# super7e.net
KiCad netlist of a schematic drawn in EAGLE
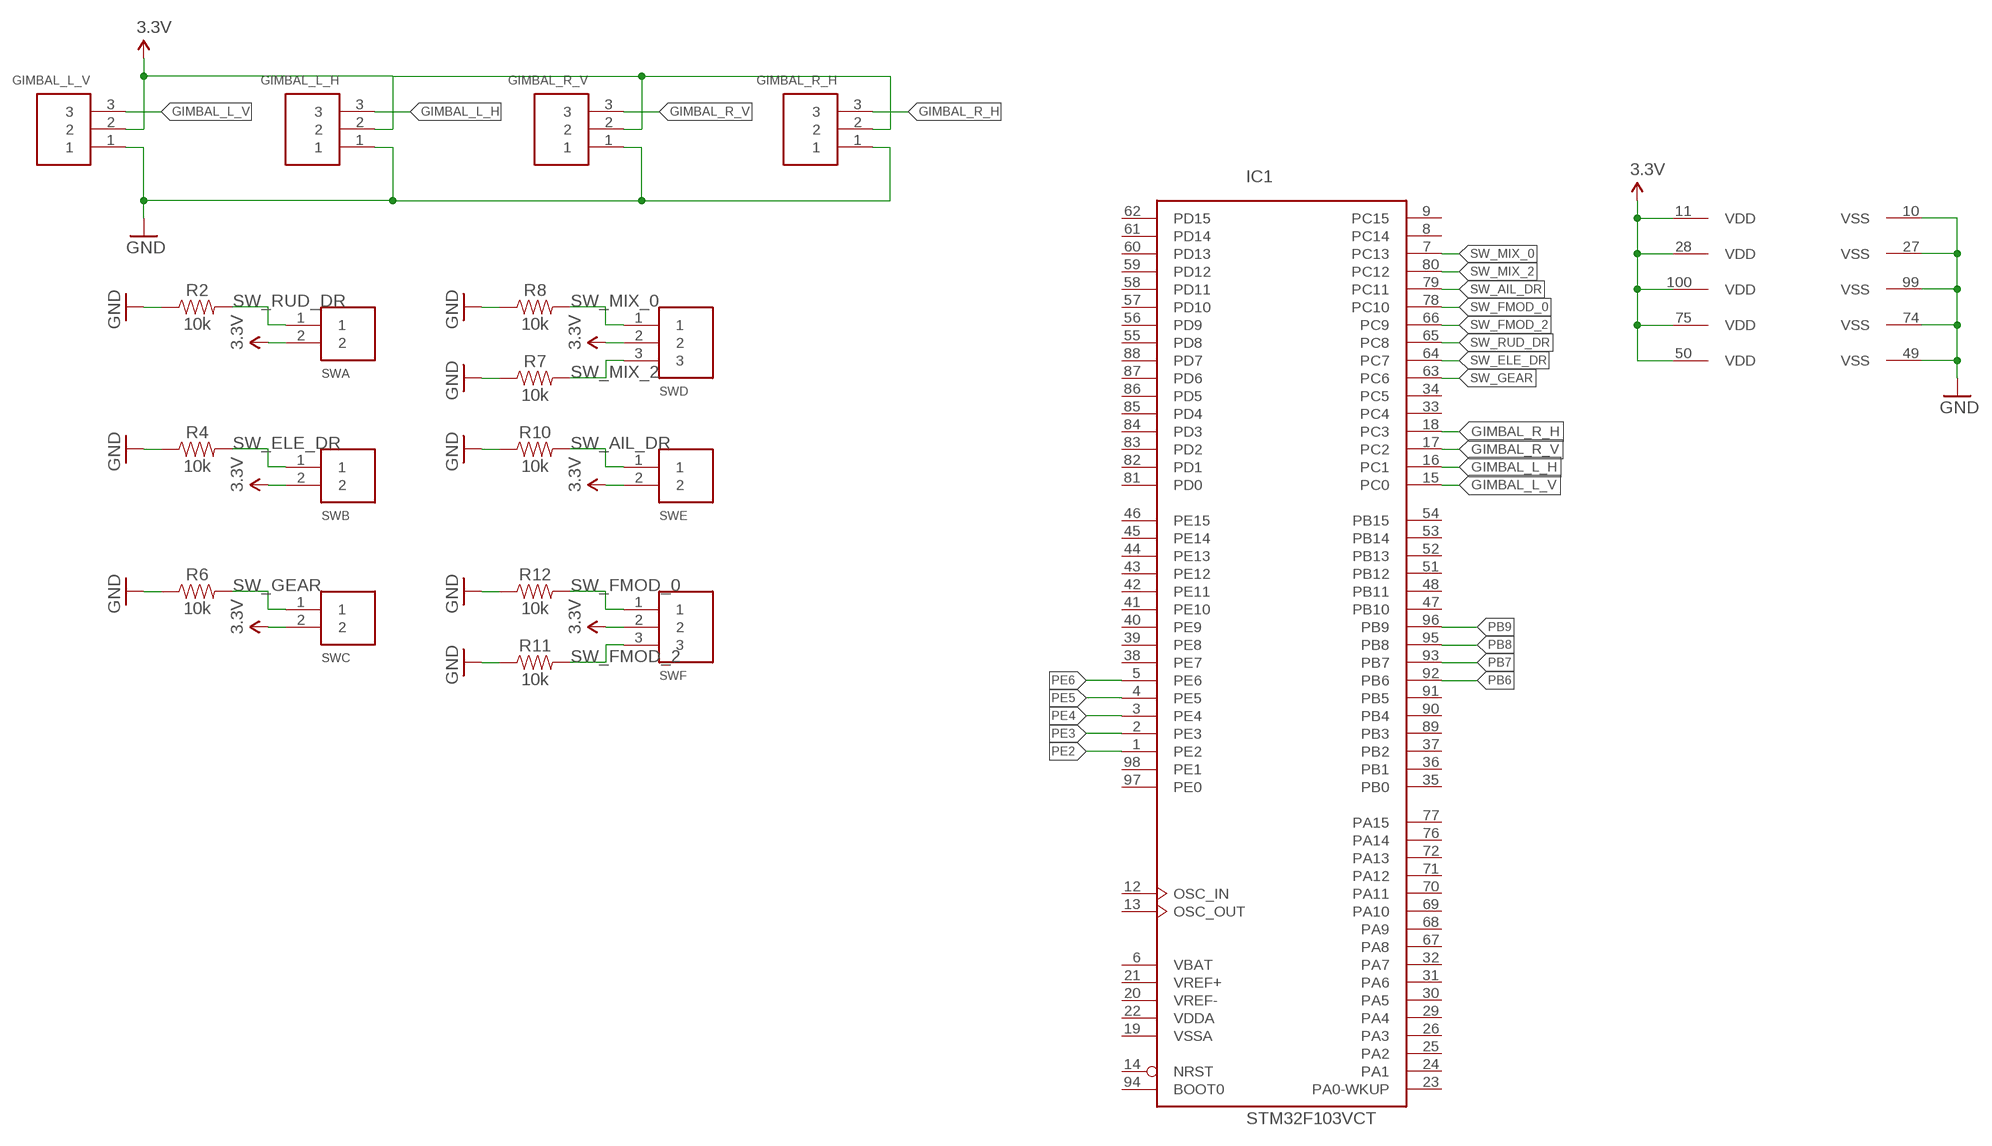
[diagram p0: schematic, sheet 1]

(export (version "E")
  (design (tool "Eeschema 10.0.6"))
  (components
    (comp (ref "GIMBAL_L_H")
      (value "3PIN")
      (footprint "eagle-import:B3B-PH-K-S")
      (libsource (lib "eagle-import") (part "3PIN"))
    )
    (comp (ref "GIMBAL_L_V")
      (value "3PIN")
      (footprint "eagle-import:B3B-PH-K-S")
      (libsource (lib "eagle-import") (part "3PIN"))
    )
    (comp (ref "GIMBAL_R_H")
      (value "3PIN")
      (footprint "eagle-import:B3B-PH-K-S")
      (libsource (lib "eagle-import") (part "3PIN"))
    )
    (comp (ref "GIMBAL_R_V")
      (value "3PIN")
      (footprint "eagle-import:B3B-PH-K-S")
      (libsource (lib "eagle-import") (part "3PIN"))
    )
    (comp (ref "IC1")
      (value "STM32F103VCT")
      (footprint "eagle-import:LQFP100")
      (libsource (lib "eagle-import") (part "STM32F103VTC"))
    )
    (comp (ref "R2")
      (value "10k")
      (footprint "eagle-import:0603")
      (libsource (lib "eagle-import") (part "10KOHM-0603-1/10W-1%"))
    )
    (comp (ref "R4")
      (value "10k")
      (footprint "eagle-import:0603")
      (libsource (lib "eagle-import") (part "10KOHM-0603-1/10W-1%"))
    )
    (comp (ref "R6")
      (value "10k")
      (footprint "eagle-import:0603")
      (libsource (lib "eagle-import") (part "10KOHM-0603-1/10W-1%"))
    )
    (comp (ref "R7")
      (value "10k")
      (footprint "eagle-import:0603")
      (libsource (lib "eagle-import") (part "10KOHM-0603-1/10W-1%"))
    )
    (comp (ref "R8")
      (value "10k")
      (footprint "eagle-import:0603")
      (libsource (lib "eagle-import") (part "10KOHM-0603-1/10W-1%"))
    )
    (comp (ref "R10")
      (value "10k")
      (footprint "eagle-import:0603")
      (libsource (lib "eagle-import") (part "10KOHM-0603-1/10W-1%"))
    )
    (comp (ref "R11")
      (value "10k")
      (footprint "eagle-import:0603")
      (libsource (lib "eagle-import") (part "10KOHM-0603-1/10W-1%"))
    )
    (comp (ref "R12")
      (value "10k")
      (footprint "eagle-import:0603")
      (libsource (lib "eagle-import") (part "10KOHM-0603-1/10W-1%"))
    )
    (comp (ref "SWA")
      (value "2PIN")
      (footprint "eagle-import:B2B-PH-K-S")
      (libsource (lib "eagle-import") (part "2PIN"))
    )
    (comp (ref "SWB")
      (value "2PIN")
      (footprint "eagle-import:B2B-PH-K-S")
      (libsource (lib "eagle-import") (part "2PIN"))
    )
    (comp (ref "SWC")
      (value "2PIN")
      (footprint "eagle-import:B2B-PH-K-S")
      (libsource (lib "eagle-import") (part "2PIN"))
    )
    (comp (ref "SWD")
      (value "3PIN")
      (footprint "eagle-import:B3B-PH-K-S")
      (libsource (lib "eagle-import") (part "3PIN"))
    )
    (comp (ref "SWE")
      (value "2PIN")
      (footprint "eagle-import:B2B-PH-K-S")
      (libsource (lib "eagle-import") (part "2PIN"))
    )
    (comp (ref "SWF")
      (value "3PIN")
      (footprint "eagle-import:B3B-PH-K-S")
      (libsource (lib "eagle-import") (part "3PIN"))
    )
  )
  (nets
    (net (code "1") (name "/VBAT") (class "Default")
      (node (ref "IC1") (pin "6") (pinfunction "VBAT_6") (pintype "power_in"))
    )
    (net (code "2") (name "/VDDA") (class "Default")
      (node (ref "IC1") (pin "22") (pinfunction "VDDA_22") (pintype "power_in"))
    )
    (net (code "3") (name "/VREF+") (class "Default")
      (node (ref "IC1") (pin "21") (pinfunction "VREF+_21") (pintype "power_in"))
    )
    (net (code "4") (name "/VREF-") (class "Default")
      (node (ref "IC1") (pin "20") (pinfunction "VREF-_20") (pintype "power_in"))
    )
    (net (code "5") (name "/VSSA") (class "Default")
      (node (ref "IC1") (pin "19") (pinfunction "VSSA_19") (pintype "power_in"))
    )
    (net (code "6") (name "3.3V") (class "Default")
      (node (ref "GIMBAL_L_H") (pin "2") (pinfunction "2_2") (pintype "bidirectional"))
      (node (ref "GIMBAL_L_V") (pin "2") (pinfunction "2_2") (pintype "bidirectional"))
      (node (ref "GIMBAL_R_H") (pin "2") (pinfunction "2_2") (pintype "bidirectional"))
      (node (ref "GIMBAL_R_V") (pin "2") (pinfunction "2_2") (pintype "bidirectional"))
      (node (ref "IC1") (pin "100") (pinfunction "VDD_100") (pintype "power_in"))
      (node (ref "IC1") (pin "11") (pinfunction "VDD_11") (pintype "power_in"))
      (node (ref "IC1") (pin "28") (pinfunction "VDD_28") (pintype "power_in"))
      (node (ref "IC1") (pin "50") (pinfunction "VDD_50") (pintype "power_in"))
      (node (ref "IC1") (pin "75") (pinfunction "VDD_75") (pintype "power_in"))
      (node (ref "SWA") (pin "2") (pinfunction "2_2") (pintype "bidirectional"))
      (node (ref "SWB") (pin "2") (pinfunction "2_2") (pintype "bidirectional"))
      (node (ref "SWC") (pin "2") (pinfunction "2_2") (pintype "bidirectional"))
      (node (ref "SWD") (pin "2") (pinfunction "2_2") (pintype "bidirectional"))
      (node (ref "SWE") (pin "2") (pinfunction "2_2") (pintype "bidirectional"))
      (node (ref "SWF") (pin "2") (pinfunction "2_2") (pintype "bidirectional"))
    )
    (net (code "7") (name "GIMBAL_L_H") (class "Default")
      (node (ref "GIMBAL_L_H") (pin "3") (pinfunction "3_3") (pintype "bidirectional"))
      (node (ref "IC1") (pin "16") (pinfunction "PC1_16") (pintype "bidirectional"))
    )
    (net (code "8") (name "GIMBAL_L_V") (class "Default")
      (node (ref "GIMBAL_L_V") (pin "3") (pinfunction "3_3") (pintype "bidirectional"))
      (node (ref "IC1") (pin "15") (pinfunction "PC0_15") (pintype "bidirectional"))
    )
    (net (code "9") (name "GIMBAL_R_H") (class "Default")
      (node (ref "GIMBAL_R_H") (pin "3") (pinfunction "3_3") (pintype "bidirectional"))
      (node (ref "IC1") (pin "18") (pinfunction "PC3_18") (pintype "bidirectional"))
    )
    (net (code "10") (name "GIMBAL_R_V") (class "Default")
      (node (ref "GIMBAL_R_V") (pin "3") (pinfunction "3_3") (pintype "bidirectional"))
      (node (ref "IC1") (pin "17") (pinfunction "PC2_17") (pintype "bidirectional"))
    )
    (net (code "11") (name "GND") (class "Default")
      (node (ref "GIMBAL_L_H") (pin "1") (pinfunction "1_1") (pintype "bidirectional"))
      (node (ref "GIMBAL_L_V") (pin "1") (pinfunction "1_1") (pintype "bidirectional"))
      (node (ref "GIMBAL_R_H") (pin "1") (pinfunction "1_1") (pintype "bidirectional"))
      (node (ref "GIMBAL_R_V") (pin "1") (pinfunction "1_1") (pintype "bidirectional"))
      (node (ref "IC1") (pin "10") (pinfunction "VSS_10") (pintype "power_in"))
      (node (ref "IC1") (pin "27") (pinfunction "VSS_27") (pintype "power_in"))
      (node (ref "IC1") (pin "49") (pinfunction "VSS_49") (pintype "power_in"))
      (node (ref "IC1") (pin "74") (pinfunction "VSS_74") (pintype "power_in"))
      (node (ref "IC1") (pin "99") (pinfunction "VSS_99") (pintype "power_in"))
      (node (ref "R10") (pin "1") (pinfunction "1_1") (pintype "passive"))
      (node (ref "R11") (pin "1") (pinfunction "1_1") (pintype "passive"))
      (node (ref "R12") (pin "1") (pinfunction "1_1") (pintype "passive"))
      (node (ref "R2") (pin "1") (pinfunction "1_1") (pintype "passive"))
      (node (ref "R4") (pin "1") (pinfunction "1_1") (pintype "passive"))
      (node (ref "R6") (pin "1") (pinfunction "1_1") (pintype "passive"))
      (node (ref "R7") (pin "1") (pinfunction "1_1") (pintype "passive"))
      (node (ref "R8") (pin "1") (pinfunction "1_1") (pintype "passive"))
    )
    (net (code "12") (name "PB6") (class "Default")
      (node (ref "IC1") (pin "92") (pinfunction "PB6_92") (pintype "bidirectional"))
    )
    (net (code "13") (name "PB7") (class "Default")
      (node (ref "IC1") (pin "93") (pinfunction "PB7_93") (pintype "bidirectional"))
    )
    (net (code "14") (name "PB8") (class "Default")
      (node (ref "IC1") (pin "95") (pinfunction "PB8_95") (pintype "bidirectional"))
    )
    (net (code "15") (name "PB9") (class "Default")
      (node (ref "IC1") (pin "96") (pinfunction "PB9_96") (pintype "bidirectional"))
    )
    (net (code "16") (name "PE2") (class "Default")
      (node (ref "IC1") (pin "1") (pinfunction "PE2_1") (pintype "bidirectional"))
    )
    (net (code "17") (name "PE3") (class "Default")
      (node (ref "IC1") (pin "2") (pinfunction "PE3_2") (pintype "bidirectional"))
    )
    (net (code "18") (name "PE4") (class "Default")
      (node (ref "IC1") (pin "3") (pinfunction "PE4_3") (pintype "bidirectional"))
    )
    (net (code "19") (name "PE5") (class "Default")
      (node (ref "IC1") (pin "4") (pinfunction "PE5_4") (pintype "bidirectional"))
    )
    (net (code "20") (name "PE6") (class "Default")
      (node (ref "IC1") (pin "5") (pinfunction "PE6_5") (pintype "bidirectional"))
    )
    (net (code "21") (name "SW_AIL_DR") (class "Default")
      (node (ref "IC1") (pin "79") (pinfunction "PC11_79") (pintype "bidirectional"))
      (node (ref "R10") (pin "2") (pinfunction "2_2") (pintype "passive"))
      (node (ref "SWE") (pin "1") (pinfunction "1_1") (pintype "bidirectional"))
    )
    (net (code "22") (name "SW_ELE_DR") (class "Default")
      (node (ref "IC1") (pin "64") (pinfunction "PC7_64") (pintype "bidirectional"))
      (node (ref "R4") (pin "2") (pinfunction "2_2") (pintype "passive"))
      (node (ref "SWB") (pin "1") (pinfunction "1_1") (pintype "bidirectional"))
    )
    (net (code "23") (name "SW_FMOD_0") (class "Default")
      (node (ref "IC1") (pin "78") (pinfunction "PC10_78") (pintype "bidirectional"))
      (node (ref "R12") (pin "2") (pinfunction "2_2") (pintype "passive"))
      (node (ref "SWF") (pin "1") (pinfunction "1_1") (pintype "bidirectional"))
    )
    (net (code "24") (name "SW_FMOD_2") (class "Default")
      (node (ref "IC1") (pin "66") (pinfunction "PC9_66") (pintype "bidirectional"))
      (node (ref "R11") (pin "2") (pinfunction "2_2") (pintype "passive"))
      (node (ref "SWF") (pin "3") (pinfunction "3_3") (pintype "bidirectional"))
    )
    (net (code "25") (name "SW_GEAR") (class "Default")
      (node (ref "IC1") (pin "63") (pinfunction "PC6_63") (pintype "bidirectional"))
      (node (ref "R6") (pin "2") (pinfunction "2_2") (pintype "passive"))
      (node (ref "SWC") (pin "1") (pinfunction "1_1") (pintype "bidirectional"))
    )
    (net (code "26") (name "SW_MIX_0") (class "Default")
      (node (ref "IC1") (pin "7") (pinfunction "PC13_7") (pintype "bidirectional"))
      (node (ref "R8") (pin "2") (pinfunction "2_2") (pintype "passive"))
      (node (ref "SWD") (pin "1") (pinfunction "1_1") (pintype "bidirectional"))
    )
    (net (code "27") (name "SW_MIX_2") (class "Default")
      (node (ref "IC1") (pin "80") (pinfunction "PC12_80") (pintype "bidirectional"))
      (node (ref "R7") (pin "2") (pinfunction "2_2") (pintype "passive"))
      (node (ref "SWD") (pin "3") (pinfunction "3_3") (pintype "bidirectional"))
    )
    (net (code "28") (name "SW_RUD_DR") (class "Default")
      (node (ref "IC1") (pin "65") (pinfunction "PC8_65") (pintype "bidirectional"))
      (node (ref "R2") (pin "2") (pinfunction "2_2") (pintype "passive"))
      (node (ref "SWA") (pin "1") (pinfunction "1_1") (pintype "bidirectional"))
    )
    (net (code "29") (name "unconnected-(IC1A-BOOT0-Pad94)") (class "Default")
      (node (ref "IC1") (pin "94") (pinfunction "BOOT0_94") (pintype "input"))
    )
    (net (code "30") (name "unconnected-(IC1A-NRST-Pad14)") (class "Default")
      (node (ref "IC1") (pin "14") (pinfunction "NRST_14") (pintype "bidirectional"))
    )
    (net (code "31") (name "unconnected-(IC1A-OSC_IN-Pad12)") (class "Default")
      (node (ref "IC1") (pin "12") (pinfunction "OSC_IN_12") (pintype "bidirectional"))
    )
    (net (code "32") (name "unconnected-(IC1A-OSC_OUT-Pad13)") (class "Default")
      (node (ref "IC1") (pin "13") (pinfunction "OSC_OUT_13") (pintype "bidirectional"))
    )
    (net (code "33") (name "unconnected-(IC1A-PA0-WKUP-Pad23)") (class "Default")
      (node (ref "IC1") (pin "23") (pinfunction "PA0-WKUP_23") (pintype "bidirectional"))
    )
    (net (code "34") (name "unconnected-(IC1A-PA1-Pad24)") (class "Default")
      (node (ref "IC1") (pin "24") (pinfunction "PA1_24") (pintype "bidirectional"))
    )
    (net (code "35") (name "unconnected-(IC1A-PA2-Pad25)") (class "Default")
      (node (ref "IC1") (pin "25") (pinfunction "PA2_25") (pintype "bidirectional"))
    )
    (net (code "36") (name "unconnected-(IC1A-PA3-Pad26)") (class "Default")
      (node (ref "IC1") (pin "26") (pinfunction "PA3_26") (pintype "bidirectional"))
    )
    (net (code "37") (name "unconnected-(IC1A-PA4-Pad29)") (class "Default")
      (node (ref "IC1") (pin "29") (pinfunction "PA4_29") (pintype "bidirectional"))
    )
    (net (code "38") (name "unconnected-(IC1A-PA5-Pad30)") (class "Default")
      (node (ref "IC1") (pin "30") (pinfunction "PA5_30") (pintype "bidirectional"))
    )
    (net (code "39") (name "unconnected-(IC1A-PA6-Pad31)") (class "Default")
      (node (ref "IC1") (pin "31") (pinfunction "PA6_31") (pintype "bidirectional"))
    )
    (net (code "40") (name "unconnected-(IC1A-PA7-Pad32)") (class "Default")
      (node (ref "IC1") (pin "32") (pinfunction "PA7_32") (pintype "bidirectional"))
    )
    (net (code "41") (name "unconnected-(IC1A-PA8-Pad67)") (class "Default")
      (node (ref "IC1") (pin "67") (pinfunction "PA8_67") (pintype "bidirectional"))
    )
    (net (code "42") (name "unconnected-(IC1A-PA9-Pad68)") (class "Default")
      (node (ref "IC1") (pin "68") (pinfunction "PA9_68") (pintype "bidirectional"))
    )
    (net (code "43") (name "unconnected-(IC1A-PA10-Pad69)") (class "Default")
      (node (ref "IC1") (pin "69") (pinfunction "PA10_69") (pintype "bidirectional"))
    )
    (net (code "44") (name "unconnected-(IC1A-PA11-Pad70)") (class "Default")
      (node (ref "IC1") (pin "70") (pinfunction "PA11_70") (pintype "bidirectional"))
    )
    (net (code "45") (name "unconnected-(IC1A-PA12-Pad71)") (class "Default")
      (node (ref "IC1") (pin "71") (pinfunction "PA12_71") (pintype "bidirectional"))
    )
    (net (code "46") (name "unconnected-(IC1A-PA13-Pad72)") (class "Default")
      (node (ref "IC1") (pin "72") (pinfunction "PA13_72") (pintype "bidirectional"))
    )
    (net (code "47") (name "unconnected-(IC1A-PA14-Pad76)") (class "Default")
      (node (ref "IC1") (pin "76") (pinfunction "PA14_76") (pintype "bidirectional"))
    )
    (net (code "48") (name "unconnected-(IC1A-PA15-Pad77)") (class "Default")
      (node (ref "IC1") (pin "77") (pinfunction "PA15_77") (pintype "bidirectional"))
    )
    (net (code "49") (name "unconnected-(IC1A-PB0-Pad35)") (class "Default")
      (node (ref "IC1") (pin "35") (pinfunction "PB0_35") (pintype "bidirectional"))
    )
    (net (code "50") (name "unconnected-(IC1A-PB1-Pad36)") (class "Default")
      (node (ref "IC1") (pin "36") (pinfunction "PB1_36") (pintype "bidirectional"))
    )
    (net (code "51") (name "unconnected-(IC1A-PB2-Pad37)") (class "Default")
      (node (ref "IC1") (pin "37") (pinfunction "PB2_37") (pintype "bidirectional"))
    )
    (net (code "52") (name "unconnected-(IC1A-PB3-Pad89)") (class "Default")
      (node (ref "IC1") (pin "89") (pinfunction "PB3_89") (pintype "bidirectional"))
    )
    (net (code "53") (name "unconnected-(IC1A-PB4-Pad90)") (class "Default")
      (node (ref "IC1") (pin "90") (pinfunction "PB4_90") (pintype "bidirectional"))
    )
    (net (code "54") (name "unconnected-(IC1A-PB5-Pad91)") (class "Default")
      (node (ref "IC1") (pin "91") (pinfunction "PB5_91") (pintype "bidirectional"))
    )
    (net (code "55") (name "unconnected-(IC1A-PB10-Pad47)") (class "Default")
      (node (ref "IC1") (pin "47") (pinfunction "PB10_47") (pintype "bidirectional"))
    )
    (net (code "56") (name "unconnected-(IC1A-PB11-Pad48)") (class "Default")
      (node (ref "IC1") (pin "48") (pinfunction "PB11_48") (pintype "bidirectional"))
    )
    (net (code "57") (name "unconnected-(IC1A-PB12-Pad51)") (class "Default")
      (node (ref "IC1") (pin "51") (pinfunction "PB12_51") (pintype "bidirectional"))
    )
    (net (code "58") (name "unconnected-(IC1A-PB13-Pad52)") (class "Default")
      (node (ref "IC1") (pin "52") (pinfunction "PB13_52") (pintype "bidirectional"))
    )
    (net (code "59") (name "unconnected-(IC1A-PB14-Pad53)") (class "Default")
      (node (ref "IC1") (pin "53") (pinfunction "PB14_53") (pintype "bidirectional"))
    )
    (net (code "60") (name "unconnected-(IC1A-PB15-Pad54)") (class "Default")
      (node (ref "IC1") (pin "54") (pinfunction "PB15_54") (pintype "bidirectional"))
    )
    (net (code "61") (name "unconnected-(IC1A-PC4-Pad33)") (class "Default")
      (node (ref "IC1") (pin "33") (pinfunction "PC4_33") (pintype "bidirectional"))
    )
    (net (code "62") (name "unconnected-(IC1A-PC5-Pad34)") (class "Default")
      (node (ref "IC1") (pin "34") (pinfunction "PC5_34") (pintype "bidirectional"))
    )
    (net (code "63") (name "unconnected-(IC1A-PC14-Pad8)") (class "Default")
      (node (ref "IC1") (pin "8") (pinfunction "PC14_8") (pintype "bidirectional"))
    )
    (net (code "64") (name "unconnected-(IC1A-PC15-Pad9)") (class "Default")
      (node (ref "IC1") (pin "9") (pinfunction "PC15_9") (pintype "bidirectional"))
    )
    (net (code "65") (name "unconnected-(IC1A-PD0-Pad81)") (class "Default")
      (node (ref "IC1") (pin "81") (pinfunction "PD0_81") (pintype "bidirectional"))
    )
    (net (code "66") (name "unconnected-(IC1A-PD1-Pad82)") (class "Default")
      (node (ref "IC1") (pin "82") (pinfunction "PD1_82") (pintype "bidirectional"))
    )
    (net (code "67") (name "unconnected-(IC1A-PD2-Pad83)") (class "Default")
      (node (ref "IC1") (pin "83") (pinfunction "PD2_83") (pintype "bidirectional"))
    )
    (net (code "68") (name "unconnected-(IC1A-PD3-Pad84)") (class "Default")
      (node (ref "IC1") (pin "84") (pinfunction "PD3_84") (pintype "bidirectional"))
    )
    (net (code "69") (name "unconnected-(IC1A-PD4-Pad85)") (class "Default")
      (node (ref "IC1") (pin "85") (pinfunction "PD4_85") (pintype "bidirectional"))
    )
    (net (code "70") (name "unconnected-(IC1A-PD5-Pad86)") (class "Default")
      (node (ref "IC1") (pin "86") (pinfunction "PD5_86") (pintype "bidirectional"))
    )
    (net (code "71") (name "unconnected-(IC1A-PD6-Pad87)") (class "Default")
      (node (ref "IC1") (pin "87") (pinfunction "PD6_87") (pintype "bidirectional"))
    )
    (net (code "72") (name "unconnected-(IC1A-PD7-Pad88)") (class "Default")
      (node (ref "IC1") (pin "88") (pinfunction "PD7_88") (pintype "bidirectional"))
    )
    (net (code "73") (name "unconnected-(IC1A-PD8-Pad55)") (class "Default")
      (node (ref "IC1") (pin "55") (pinfunction "PD8_55") (pintype "bidirectional"))
    )
    (net (code "74") (name "unconnected-(IC1A-PD9-Pad56)") (class "Default")
      (node (ref "IC1") (pin "56") (pinfunction "PD9_56") (pintype "bidirectional"))
    )
    (net (code "75") (name "unconnected-(IC1A-PD10-Pad57)") (class "Default")
      (node (ref "IC1") (pin "57") (pinfunction "PD10_57") (pintype "bidirectional"))
    )
    (net (code "76") (name "unconnected-(IC1A-PD11-Pad58)") (class "Default")
      (node (ref "IC1") (pin "58") (pinfunction "PD11_58") (pintype "bidirectional"))
    )
    (net (code "77") (name "unconnected-(IC1A-PD12-Pad59)") (class "Default")
      (node (ref "IC1") (pin "59") (pinfunction "PD12_59") (pintype "bidirectional"))
    )
    (net (code "78") (name "unconnected-(IC1A-PD13-Pad60)") (class "Default")
      (node (ref "IC1") (pin "60") (pinfunction "PD13_60") (pintype "bidirectional"))
    )
    (net (code "79") (name "unconnected-(IC1A-PD14-Pad61)") (class "Default")
      (node (ref "IC1") (pin "61") (pinfunction "PD14_61") (pintype "bidirectional"))
    )
    (net (code "80") (name "unconnected-(IC1A-PD15-Pad62)") (class "Default")
      (node (ref "IC1") (pin "62") (pinfunction "PD15_62") (pintype "bidirectional"))
    )
    (net (code "81") (name "unconnected-(IC1A-PE0-Pad97)") (class "Default")
      (node (ref "IC1") (pin "97") (pinfunction "PE0_97") (pintype "bidirectional"))
    )
    (net (code "82") (name "unconnected-(IC1A-PE1-Pad98)") (class "Default")
      (node (ref "IC1") (pin "98") (pinfunction "PE1_98") (pintype "bidirectional"))
    )
    (net (code "83") (name "unconnected-(IC1A-PE7-Pad38)") (class "Default")
      (node (ref "IC1") (pin "38") (pinfunction "PE7_38") (pintype "bidirectional"))
    )
    (net (code "84") (name "unconnected-(IC1A-PE8-Pad39)") (class "Default")
      (node (ref "IC1") (pin "39") (pinfunction "PE8_39") (pintype "bidirectional"))
    )
    (net (code "85") (name "unconnected-(IC1A-PE9-Pad40)") (class "Default")
      (node (ref "IC1") (pin "40") (pinfunction "PE9_40") (pintype "bidirectional"))
    )
    (net (code "86") (name "unconnected-(IC1A-PE10-Pad41)") (class "Default")
      (node (ref "IC1") (pin "41") (pinfunction "PE10_41") (pintype "bidirectional"))
    )
    (net (code "87") (name "unconnected-(IC1A-PE11-Pad42)") (class "Default")
      (node (ref "IC1") (pin "42") (pinfunction "PE11_42") (pintype "bidirectional"))
    )
    (net (code "88") (name "unconnected-(IC1A-PE12-Pad43)") (class "Default")
      (node (ref "IC1") (pin "43") (pinfunction "PE12_43") (pintype "bidirectional"))
    )
    (net (code "89") (name "unconnected-(IC1A-PE13-Pad44)") (class "Default")
      (node (ref "IC1") (pin "44") (pinfunction "PE13_44") (pintype "bidirectional"))
    )
    (net (code "90") (name "unconnected-(IC1A-PE14-Pad45)") (class "Default")
      (node (ref "IC1") (pin "45") (pinfunction "PE14_45") (pintype "bidirectional"))
    )
    (net (code "91") (name "unconnected-(IC1A-PE15-Pad46)") (class "Default")
      (node (ref "IC1") (pin "46") (pinfunction "PE15_46") (pintype "bidirectional"))
    )
  )
)
